# schem.net
KiCad netlist of a schematic drawn in Altium Designer
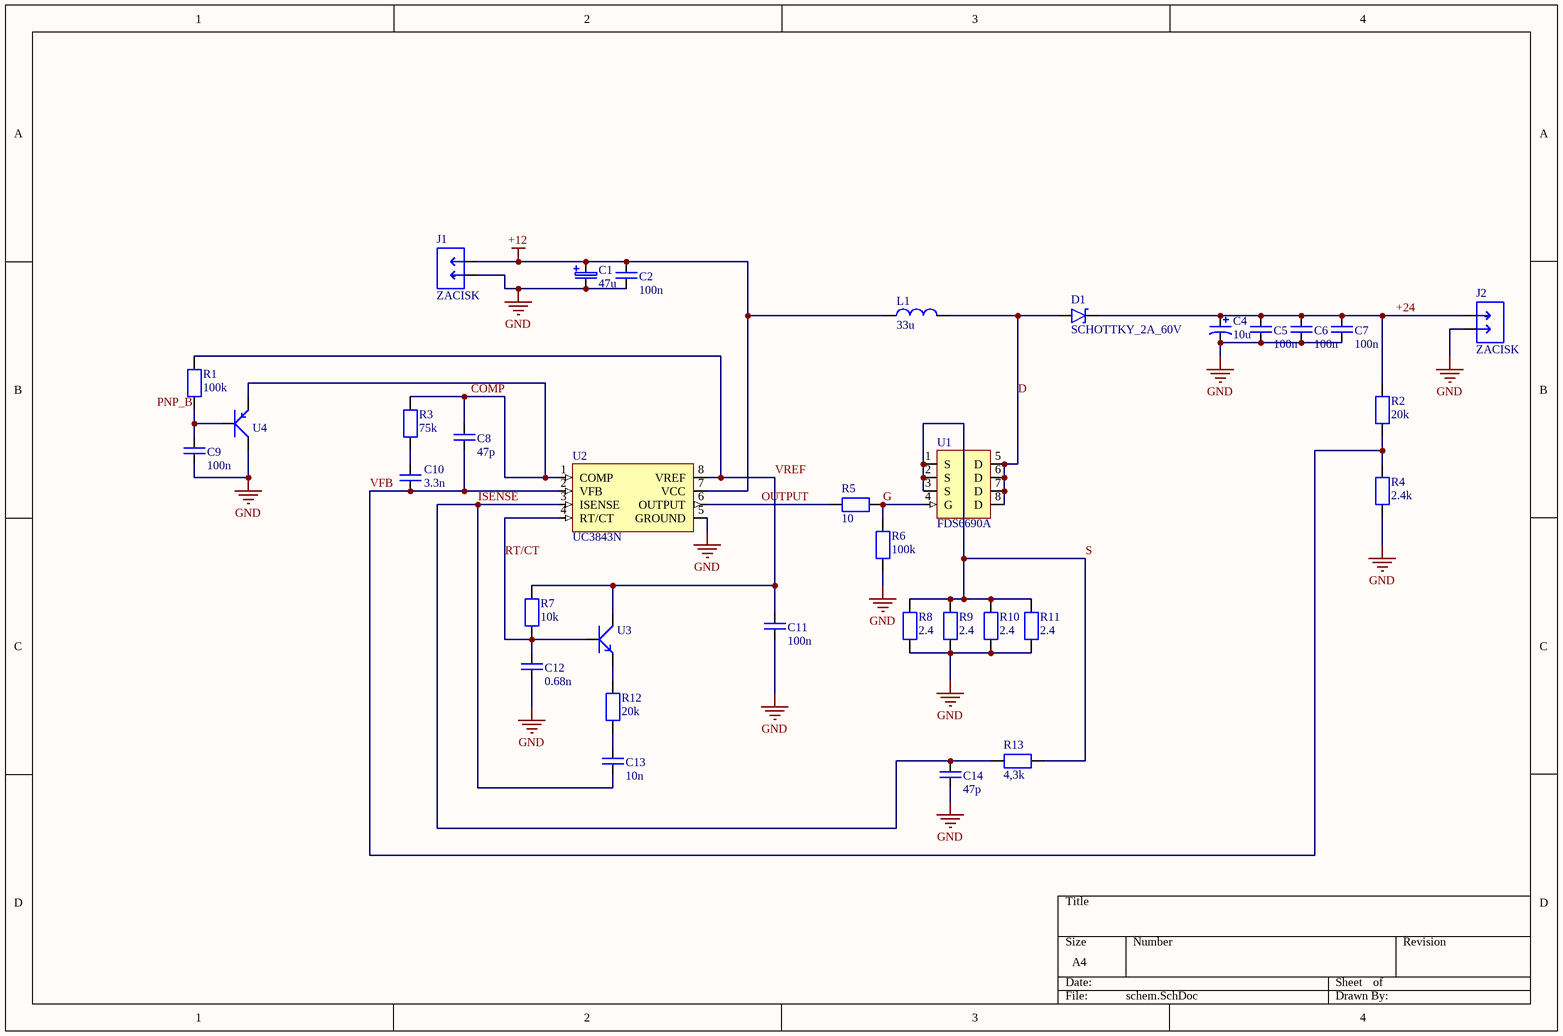
[diagram p0: schem.SchDoc]

(export (version "E")
  (design (tool "Eeschema 10.0.6"))
  (components
    (comp (ref "C1")
      (value "47u")
      (footprint "CAP_ALUM")
      (description "Kondensator: elektrolityczny; SMD; 47uF; 16VDC; Ø5x5,3mm; ±20%")
      (fields (field (name "TOLERANCE") "20%") (field (name "VOLTAGE") "63V"))
      (libsource (lib "Schem_lib") (part "CAP_47uF_16V_ALUM"))
    )
    (comp (ref "C2")
      (value "100n")
      (footprint "CAP_0805_CER")
      (description "Kondensator: ceramiczny; MLCC; 100nF; 50V; X7R; ±10%; SMD; 0805")
      (libsource (lib "Schem_lib") (part "CAP_100nF_ 0805_CER"))
    )
    (comp (ref "C4")
      (value "10u")
      (footprint "CAP_TANTAL_1210")
      (description "Kondensator: tantalowo-polimerowy; low ESR; 10uF; 35VDC; B; 1210")
      (libsource (lib "Schem_lib") (part "CAP_10uF_1210_TANTALUM"))
    )
    (comp (ref "C5")
      (value "100n")
      (footprint "CAP_0805_CER")
      (description "Kondensator: ceramiczny; MLCC; 100nF; 50V; X7R; ±10%; SMD; 0805")
      (libsource (lib "Schem_lib") (part "CAP_100nF_ 0805_CER"))
    )
    (comp (ref "C6")
      (value "100n")
      (footprint "CAP_0805_CER")
      (description "Kondensator: ceramiczny; MLCC; 100nF; 50V; X7R; ±10%; SMD; 0805")
      (libsource (lib "Schem_lib") (part "CAP_100nF_ 0805_CER"))
    )
    (comp (ref "C7")
      (value "100n")
      (footprint "CAP_0805_CER")
      (description "Kondensator: ceramiczny; MLCC; 100nF; 50V; X7R; ±10%; SMD; 0805")
      (libsource (lib "Schem_lib") (part "CAP_100nF_ 0805_CER"))
    )
    (comp (ref "C8")
      (value "47p")
      (footprint "CAP_0805_CER")
      (description "Kondensator: ceramiczny; MLCC; 47pF; 50V; C0G (NP0); ±5%; SMD; 0805")
      (libsource (lib "Schem_lib") (part "CAP_47pF_ 0805_CER"))
    )
    (comp (ref "C9")
      (value "100n")
      (footprint "CAP_0805_CER")
      (description "Kondensator: ceramiczny; MLCC; 100nF; 50V; X7R; ±10%; SMD; 0805")
      (libsource (lib "Schem_lib") (part "CAP_100nF_ 0805_CER"))
    )
    (comp (ref "C10")
      (value "3.3n")
      (footprint "CAP_0805_CER")
      (description "Kondensator: ceramiczny; MLCC; 3,3nF; 200V; C0G (NP0); ±5%; SMD")
      (libsource (lib "Schem_lib") (part "CAP_3,3nF_0805_CER"))
    )
    (comp (ref "C11")
      (value "100n")
      (footprint "CAP_0805_CER")
      (description "Kondensator: ceramiczny; MLCC; 100nF; 50V; X7R; ±10%; SMD; 0805")
      (libsource (lib "Schem_lib") (part "CAP_100nF_ 0805_CER"))
    )
    (comp (ref "C12")
      (value "0.68n")
      (footprint "CAP_0805_CER")
      (description "Kondensator: ceramiczny; MLCC; 680pF; 50V; C0G (NP0); ±5%; SMD; 0805")
      (libsource (lib "Schem_lib") (part "CAP_680pF_0805_CER"))
    )
    (comp (ref "C13")
      (value "10n")
      (footprint "CAP_0805_CER")
      (description "Kondensator: ceramiczny; MLCC; 10nF; 50V; C0G (NP0); ±5%; SMD; 0805")
      (libsource (lib "Schem_lib") (part "CAP_10nF_0805_CER"))
    )
    (comp (ref "C14")
      (value "47p")
      (footprint "CAP_0805_CER")
      (description "Kondensator: ceramiczny; MLCC; 47pF; 50V; C0G (NP0); ±5%; SMD; 0805")
      (libsource (lib "Schem_lib") (part "CAP_47pF_ 0805_CER"))
    )
    (comp (ref "D1")
      (value "SCHOTTKY_2A_60V")
      (footprint "23SCHOTTKY_60V_2A")
      (description "Dioda: prostownicza Schottky; SMA; SMD; 60V; 2A; rolka,taśma")
      (fields
        (field (name "MANUFACTURER") "STMicroelectronics")
        (field (name "MANUFACTURER PART NUMBER") "STPS2L60A")
      )
      (libsource (lib "Schem_lib") (part "SCHOTTKY_2A_60V"))
    )
    (comp (ref "J1") (value "ZACISK") (footprint "Zacisk") (libsource (lib "Schem_lib") (part "ZACISK")))
    (comp (ref "J2") (value "ZACISK") (footprint "Zacisk") (libsource (lib "Schem_lib") (part "ZACISK")))
    (comp (ref "L1")
      (value "33u")
      (footprint "DL50-33")
      (description "Dławik: drutowy; SMD; 33uH; Ipracy: 3A; R: 0,066Ω; Isat: 5,5A")
      (fields (field (name "MANUFACTURER") "Eaton") (field (name "MANUFACTURER PART NUMBER") "DRA127-330-R"))
      (libsource (lib "Schem_lib") (part "IND_33uH_3A"))
    )
    (comp (ref "R1")
      (value "100k")
      (footprint "RES_0805")
      (description "Rezystor: thick film; SMD; 0805; 100kΩ; 0,125W; ±1%; RC; 150V")
      (libsource (lib "Schem_lib") (part "RES_100kΩ_0805"))
    )
    (comp (ref "R2")
      (value "20k")
      (footprint "RES_0805")
      (description "Rezystor: thick film; SMD; 0805; 20kΩ; 0,125W; ±1%; 150V; -55÷155°C")
      (libsource (lib "Schem_lib") (part "RES_20kΩ_0805"))
    )
    (comp (ref "R3")
      (value "75k")
      (footprint "RES_0805")
      (description "Rezystor: thick film; SMD; 0805; 75kΩ; 0,125W; ±1%; 150V; -55÷155°C")
      (libsource (lib "Schem_lib") (part "RES_75kΩ_0805"))
    )
    (comp (ref "R4")
      (value "2.4k")
      (footprint "RES_0805")
      (description "Rezystor: thick film; SMD; 0805; 2,4kΩ; 0,125W; ±5%; 150V; -55÷155°C")
      (libsource (lib "Schem_lib") (part "RES_2,4kΩ_0805"))
    )
    (comp (ref "R5")
      (value "10")
      (footprint "RES_0805")
      (description "Rezystor: thick film; SMD; 0805; 10Ω; 250mW; ±5%; 150V; -55÷125°C")
      (libsource (lib "Schem_lib") (part "RES_10Ω_0805"))
    )
    (comp (ref "R6")
      (value "100k")
      (footprint "RES_0805")
      (description "Rezystor: thick film; SMD; 0805; 100kΩ; 0,125W; ±1%; RC; 150V")
      (libsource (lib "Schem_lib") (part "RES_100kΩ_0805"))
    )
    (comp (ref "R7")
      (value "10k")
      (footprint "RES_0805")
      (description "Rezystor: thin film; precyzyjny; SMD; 0805; 10kΩ; 0,125W; ±0,1%")
      (libsource (lib "Schem_lib") (part "RES_10kΩ_0805"))
    )
    (comp (ref "R8")
      (value "2.4")
      (footprint "RES_1206")
      (description "Rezystor: thick film; SMD; 1206; 2,4Ω; 0,25W; ±1%; 200V; -55÷155°C")
      (libsource (lib "Schem_lib") (part "RES_2,4Ω_1206"))
    )
    (comp (ref "R9")
      (value "2.4")
      (footprint "RES_1206")
      (description "Rezystor: thick film; SMD; 1206; 2,4Ω; 0,25W; ±1%; 200V; -55÷155°C")
      (libsource (lib "Schem_lib") (part "RES_2,4Ω_1206"))
    )
    (comp (ref "R10")
      (value "2.4")
      (footprint "RES_1206")
      (description "Rezystor: thick film; SMD; 1206; 2,4Ω; 0,25W; ±1%; 200V; -55÷155°C")
      (libsource (lib "Schem_lib") (part "RES_2,4Ω_1206"))
    )
    (comp (ref "R11")
      (value "2.4")
      (footprint "RES_1206")
      (description "Rezystor: thick film; SMD; 1206; 2,4Ω; 0,25W; ±1%; 200V; -55÷155°C")
      (libsource (lib "Schem_lib") (part "RES_2,4Ω_1206"))
    )
    (comp (ref "R12")
      (value "20k")
      (footprint "RES_0805")
      (description "Rezystor: thick film; SMD; 0805; 20kΩ; 0,125W; ±1%; 150V; -55÷155°C")
      (libsource (lib "Schem_lib") (part "RES_20kΩ_0805"))
    )
    (comp (ref "R13")
      (value "4,3k")
      (footprint "RES_0805")
      (description "Rezystor: thick film; SMD; 0805; 4,3kΩ; 0,125W; ±5%; 150V; -55÷155°C")
      (libsource (lib "Schem_lib") (part "RES_4,3kΩ_0805"))
    )
    (comp (ref "U1")
      (value "FDS6690A")
      (footprint "FDS6690A")
      (libsource (lib "Schem_lib") (part "FDS6690A"))
    )
    (comp (ref "U2") (value "UC3843N") (footprint "UC3843N") (libsource (lib "Schem_lib") (part "UC3843N")))
    (comp (ref "U3")
      (value "NPN_MMBT3904LT1G")
      (footprint "NPN")
      (libsource (lib "Schem_lib") (part "NPN_MMBT3904LT1G"))
    )
    (comp (ref "U4")
      (value "PNP_BC807-25LT1G")
      (footprint "PNP")
      (libsource (lib "Schem_lib") (part "PNP_BC807-25LT1G"))
    )
  )
  (nets
    (net (code "1") (name "+12") (class "Default")
      (node (ref "C1") (pin "2") (pintype "passive"))
      (node (ref "C2") (pin "2") (pintype "passive"))
      (node (ref "J1") (pin "1") (pinfunction "+_1") (pintype "passive"))
      (node (ref "L1") (pin "1") (pintype "passive"))
      (node (ref "U2") (pin "7") (pinfunction "VCC_7") (pintype "power_in"))
    )
    (net (code "2") (name "/+24") (class "Default")
      (node (ref "C4") (pin "2") (pintype "passive"))
      (node (ref "C5") (pin "2") (pintype "passive"))
      (node (ref "C6") (pin "2") (pintype "passive"))
      (node (ref "C7") (pin "2") (pintype "passive"))
      (node (ref "D1") (pin "1") (pinfunction "1_1") (pintype "passive"))
      (node (ref "J2") (pin "2") (pinfunction "-_2") (pintype "passive"))
      (node (ref "R2") (pin "2") (pintype "passive"))
    )
    (net (code "3") (name "/COMP") (class "Default")
      (node (ref "C8") (pin "2") (pintype "passive"))
      (node (ref "R3") (pin "1") (pintype "passive"))
      (node (ref "U2") (pin "1") (pinfunction "COMP_1") (pintype "input"))
      (node (ref "U4") (pin "2") (pinfunction "2_2") (pintype "passive"))
    )
    (net (code "4") (name "/D") (class "Default")
      (node (ref "D1") (pin "2") (pinfunction "2_2") (pintype "passive"))
      (node (ref "L1") (pin "2") (pintype "passive"))
      (node (ref "U1") (pin "5") (pinfunction "D_5") (pintype "open_emitter"))
      (node (ref "U1") (pin "6") (pinfunction "D_6") (pintype "power_in"))
      (node (ref "U1") (pin "7") (pinfunction "D_7") (pintype "power_in"))
      (node (ref "U1") (pin "8") (pinfunction "D_8") (pintype "power_in"))
    )
    (net (code "5") (name "/G") (class "Default")
      (node (ref "R5") (pin "2") (pintype "passive"))
      (node (ref "R6") (pin "2") (pintype "passive"))
      (node (ref "U1") (pin "4") (pinfunction "G_4") (pintype "input"))
    )
    (net (code "6") (name "/ISENSE") (class "Default")
      (node (ref "C13") (pin "1") (pintype "passive"))
      (node (ref "C14") (pin "2") (pintype "passive"))
      (node (ref "R13") (pin "1") (pintype "passive"))
      (node (ref "U2") (pin "3") (pinfunction "ISENSE_3") (pintype "input"))
    )
    (net (code "7") (name "/OUTPUT") (class "Default")
      (node (ref "R5") (pin "1") (pintype "passive"))
      (node (ref "U2") (pin "6") (pinfunction "OUTPUT_6") (pintype "output"))
    )
    (net (code "8") (name "/PNP_B") (class "Default")
      (node (ref "C9") (pin "2") (pintype "passive"))
      (node (ref "R1") (pin "1") (pintype "passive"))
      (node (ref "U4") (pin "1") (pinfunction "1_1") (pintype "passive"))
    )
    (net (code "9") (name "/RT{slash}CT") (class "Default")
      (node (ref "C12") (pin "1") (pintype "passive"))
      (node (ref "R7") (pin "1") (pintype "passive"))
      (node (ref "U2") (pin "4") (pinfunction "RT/CT_4") (pintype "input"))
      (node (ref "U3") (pin "1") (pinfunction "1_1") (pintype "passive"))
    )
    (net (code "10") (name "/S") (class "Default")
      (node (ref "R10") (pin "2") (pintype "passive"))
      (node (ref "R11") (pin "2") (pintype "passive"))
      (node (ref "R13") (pin "2") (pintype "passive"))
      (node (ref "R8") (pin "2") (pintype "passive"))
      (node (ref "R9") (pin "2") (pintype "passive"))
      (node (ref "U1") (pin "1") (pinfunction "S_1") (pintype "power_in"))
      (node (ref "U1") (pin "2") (pinfunction "S_2") (pintype "power_in"))
      (node (ref "U1") (pin "3") (pinfunction "S_3") (pintype "power_in"))
    )
    (net (code "11") (name "/VFB") (class "Default")
      (node (ref "C10") (pin "2") (pintype "passive"))
      (node (ref "C8") (pin "1") (pintype "passive"))
      (node (ref "R2") (pin "1") (pintype "passive"))
      (node (ref "R4") (pin "2") (pintype "passive"))
      (node (ref "U2") (pin "2") (pinfunction "VFB_2") (pintype "input"))
    )
    (net (code "12") (name "/VREF") (class "Default")
      (node (ref "C11") (pin "2") (pintype "passive"))
      (node (ref "R1") (pin "2") (pintype "passive"))
      (node (ref "R7") (pin "2") (pintype "passive"))
      (node (ref "U2") (pin "8") (pinfunction "VREF_8") (pintype "power_in"))
      (node (ref "U3") (pin "3") (pinfunction "3_3") (pintype "passive"))
    )
    (net (code "13") (name "GND") (class "Default")
      (node (ref "C1") (pin "1") (pintype "passive"))
      (node (ref "C11") (pin "1") (pintype "passive"))
      (node (ref "C12") (pin "2") (pintype "passive"))
      (node (ref "C14") (pin "1") (pintype "passive"))
      (node (ref "C2") (pin "1") (pintype "passive"))
      (node (ref "C4") (pin "1") (pintype "passive"))
      (node (ref "C5") (pin "1") (pintype "passive"))
      (node (ref "C6") (pin "1") (pintype "passive"))
      (node (ref "C7") (pin "1") (pintype "passive"))
      (node (ref "C9") (pin "1") (pintype "passive"))
      (node (ref "J1") (pin "2") (pinfunction "-_2") (pintype "passive"))
      (node (ref "J2") (pin "1") (pinfunction "+_1") (pintype "passive"))
      (node (ref "R10") (pin "1") (pintype "passive"))
      (node (ref "R11") (pin "1") (pintype "passive"))
      (node (ref "R4") (pin "1") (pintype "passive"))
      (node (ref "R6") (pin "1") (pintype "passive"))
      (node (ref "R8") (pin "1") (pintype "passive"))
      (node (ref "R9") (pin "1") (pintype "passive"))
      (node (ref "U2") (pin "5") (pinfunction "GROUND_5") (pintype "power_in"))
      (node (ref "U4") (pin "3") (pinfunction "3_3") (pintype "passive"))
    )
    (net (code "14") (name "Net-(C10-Pad1)") (class "Default")
      (node (ref "C10") (pin "1") (pintype "passive"))
      (node (ref "R3") (pin "2") (pintype "passive"))
    )
    (net (code "15") (name "Net-(C13-Pad2)") (class "Default")
      (node (ref "C13") (pin "2") (pintype "passive"))
      (node (ref "R12") (pin "1") (pintype "passive"))
    )
    (net (code "16") (name "Net-(R12-Pad2)") (class "Default")
      (node (ref "R12") (pin "2") (pintype "passive"))
      (node (ref "U3") (pin "2") (pinfunction "2_2") (pintype "passive"))
    )
  )
)
